# MAZ000157_-_Diagrama_el_ctrico.net
KiCad netlist of a schematic drawn in Altium Designer
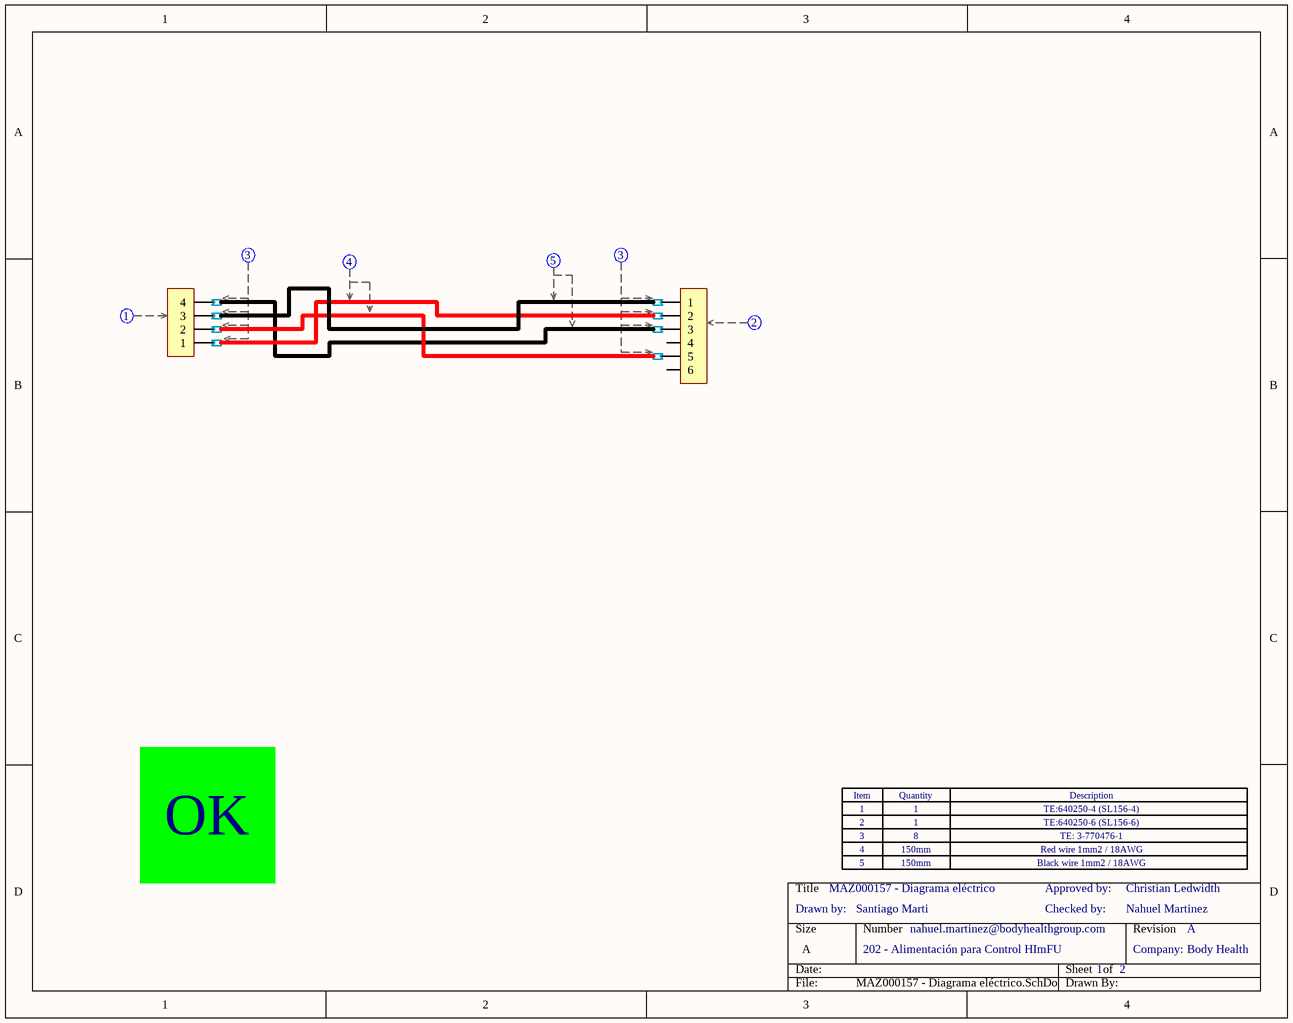
[diagram p0: MAZ000157 - Diagrama eléctrico.SchDoc]

(export (version "E")
  (design (tool "Eeschema 10.0.6"))
  (components
    (comp (ref "Con1")
      (value "SL156-4")
      (description "CONN RECEPT 4 POS W/RAMP SL-156")
      (libsource (lib "LibreriaParaPlanos") (part "SL156-4"))
    )
    (comp (ref "Con2")
      (value "SL156-6")
      (description "CONN RECEPT 6 POS W/RAMP SL-156")
      (libsource (lib "LibreriaParaPlanos") (part "SL156-6"))
    )
    (comp (ref "Soc1")
      (value "sock_SL156_770476-1")
      (description "CONN SOCKET 18-24AWG CRIMP TIN")
      (libsource (lib "LibreriaParaPlanos") (part "sock_SL156_770476-1"))
    )
    (comp (ref "Soc2")
      (value "sock_SL156_770476-1")
      (description "CONN SOCKET 18-24AWG CRIMP TIN")
      (libsource (lib "LibreriaParaPlanos") (part "sock_SL156_770476-1"))
    )
    (comp (ref "Soc3")
      (value "sock_SL156_770476-1")
      (description "CONN SOCKET 18-24AWG CRIMP TIN")
      (libsource (lib "LibreriaParaPlanos") (part "sock_SL156_770476-1"))
    )
    (comp (ref "Soc4")
      (value "sock_SL156_770476-1")
      (description "CONN SOCKET 18-24AWG CRIMP TIN")
      (libsource (lib "LibreriaParaPlanos") (part "sock_SL156_770476-1"))
    )
    (comp (ref "Soc5")
      (value "sock_SL156_770476-1")
      (description "CONN SOCKET 18-24AWG CRIMP TIN")
      (libsource (lib "LibreriaParaPlanos") (part "sock_SL156_770476-1"))
    )
    (comp (ref "Soc6")
      (value "sock_SL156_770476-1")
      (description "CONN SOCKET 18-24AWG CRIMP TIN")
      (libsource (lib "LibreriaParaPlanos") (part "sock_SL156_770476-1"))
    )
    (comp (ref "Soc7")
      (value "sock_SL156_770476-1")
      (description "CONN SOCKET 18-24AWG CRIMP TIN")
      (libsource (lib "LibreriaParaPlanos") (part "sock_SL156_770476-1"))
    )
    (comp (ref "Soc8")
      (value "sock_SL156_770476-1")
      (description "CONN SOCKET 18-24AWG CRIMP TIN")
      (libsource (lib "LibreriaParaPlanos") (part "sock_SL156_770476-1"))
    )
    (comp (ref "Zoc1")
      (value "Zócalo_Header")
      (description "Header para el zócalo de referencias")
      (libsource (lib "LibreriaParaPlanos") (part "Zócalo_Header"))
    )
    (comp (ref "Zoc2")
      (value "Zócalo_Item")
      (description "Ítem para el zócalo de referencias")
      (libsource (lib "LibreriaParaPlanos") (part "Zócalo_Item"))
    )
    (comp (ref "Zoc3")
      (value "Zócalo_Item")
      (description "Ítem para el zócalo de referencias")
      (libsource (lib "LibreriaParaPlanos") (part "Zócalo_Item"))
    )
    (comp (ref "Zoc4")
      (value "Zócalo_Item")
      (description "Ítem para el zócalo de referencias")
      (libsource (lib "LibreriaParaPlanos") (part "Zócalo_Item"))
    )
    (comp (ref "Zoc5")
      (value "Zócalo_Item")
      (description "Ítem para el zócalo de referencias")
      (libsource (lib "LibreriaParaPlanos") (part "Zócalo_Item"))
    )
    (comp (ref "Zoc6")
      (value "Zócalo_Item")
      (description "Ítem para el zócalo de referencias")
      (libsource (lib "LibreriaParaPlanos") (part "Zócalo_Item"))
    )
  )
  (nets
    (net (code "1") (name "Net-(Con1-Pad1)") (class "Default")
      (node (ref "Con1") (pin "1") (pinfunction "1_1") (pintype "passive"))
      (node (ref "Soc7") (pin "0") (pinfunction "0_0") (pintype "passive"))
    )
    (net (code "2") (name "Net-(Con1-Pad2)") (class "Default")
      (node (ref "Con1") (pin "2") (pinfunction "2_2") (pintype "passive"))
      (node (ref "Soc5") (pin "0") (pinfunction "0_0") (pintype "passive"))
    )
    (net (code "3") (name "Net-(Con1-Pad3)") (class "Default")
      (node (ref "Con1") (pin "3") (pinfunction "3_3") (pintype "passive"))
      (node (ref "Soc3") (pin "0") (pinfunction "0_0") (pintype "passive"))
    )
    (net (code "4") (name "Net-(Con1-Pad4)") (class "Default")
      (node (ref "Con1") (pin "4") (pinfunction "4_4") (pintype "passive"))
      (node (ref "Soc1") (pin "0") (pinfunction "0_0") (pintype "passive"))
    )
    (net (code "5") (name "Net-(Con2-Pad1)") (class "Default")
      (node (ref "Con2") (pin "1") (pinfunction "1_1") (pintype "passive"))
      (node (ref "Soc2") (pin "0") (pinfunction "0_0") (pintype "passive"))
    )
    (net (code "6") (name "Net-(Con2-Pad2)") (class "Default")
      (node (ref "Con2") (pin "2") (pinfunction "2_2") (pintype "passive"))
      (node (ref "Soc4") (pin "0") (pinfunction "0_0") (pintype "passive"))
    )
    (net (code "7") (name "Net-(Con2-Pad3)") (class "Default")
      (node (ref "Con2") (pin "3") (pinfunction "3_3") (pintype "passive"))
      (node (ref "Soc6") (pin "0") (pinfunction "0_0") (pintype "passive"))
    )
    (net (code "8") (name "Net-(Con2-Pad5)") (class "Default")
      (node (ref "Con2") (pin "5") (pinfunction "5_5") (pintype "passive"))
      (node (ref "Soc8") (pin "0") (pinfunction "0_0") (pintype "passive"))
    )
    (net (code "9") (name "Net-(Soc1-Pad1)") (class "Default")
      (node (ref "Soc1") (pin "1") (pinfunction "1_1") (pintype "passive"))
      (node (ref "Soc6") (pin "1") (pinfunction "1_1") (pintype "passive"))
    )
    (net (code "10") (name "Net-(Soc2-Pad1)") (class "Default")
      (node (ref "Soc2") (pin "1") (pinfunction "1_1") (pintype "passive"))
      (node (ref "Soc3") (pin "1") (pinfunction "1_1") (pintype "passive"))
    )
    (net (code "11") (name "Net-(Soc4-Pad1)") (class "Default")
      (node (ref "Soc4") (pin "1") (pinfunction "1_1") (pintype "passive"))
      (node (ref "Soc7") (pin "1") (pinfunction "1_1") (pintype "passive"))
    )
    (net (code "12") (name "Net-(Soc5-Pad1)") (class "Default")
      (node (ref "Soc5") (pin "1") (pinfunction "1_1") (pintype "passive"))
      (node (ref "Soc8") (pin "1") (pinfunction "1_1") (pintype "passive"))
    )
    (net (code "13") (name "unconnected-(Con2-Pad4)") (class "Default")
      (node (ref "Con2") (pin "4") (pinfunction "4_4") (pintype "passive"))
    )
    (net (code "14") (name "unconnected-(Con2-Pad6)") (class "Default")
      (node (ref "Con2") (pin "6") (pinfunction "6_6") (pintype "passive"))
    )
  )
)
